# crystal.net
KiCad netlist of a schematic drawn in Altium Designer
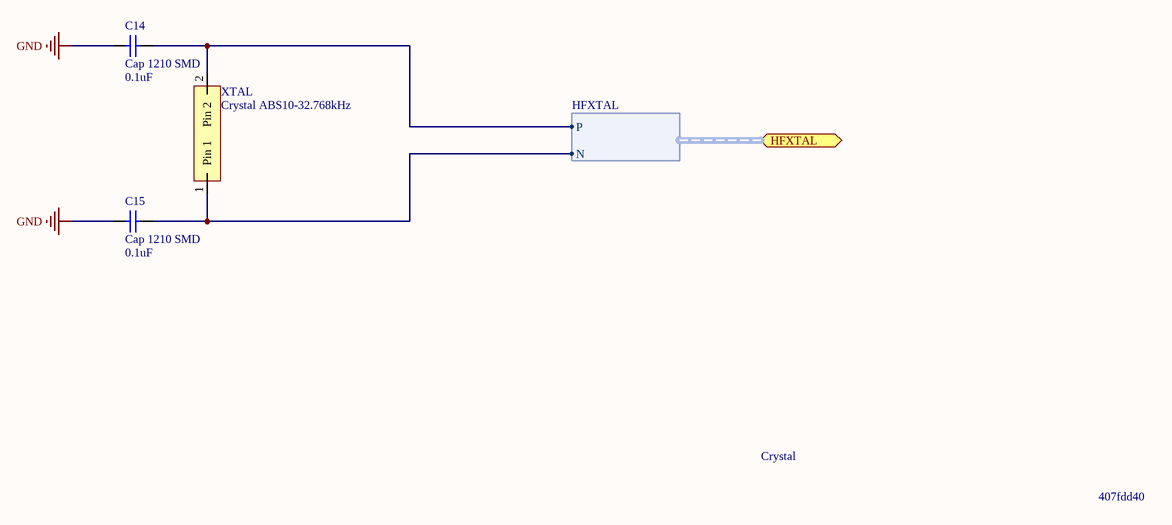
[diagram p0: crystal.schdoc]

(export (version "E")
  (design (tool "Eeschema 10.0.6"))
  (components
    (comp (ref "C14")
      (value "Cap 1210 SMD")
      (footprint "CAPC1210(3225)100_L")
      (description "CAP 0.1uF 100V ±1% 1210 (3225 Metric) Thickness 1mm SMD")
      (fields (field (name "ALTIUM_VALUE") "0.1uF") (field (name "TOLERANCE") "±1%"))
      (libsource (lib "Altium Content Vault") (part "CMP-1038-00186-1"))
    )
    (comp (ref "C15")
      (value "Cap 1210 SMD")
      (footprint "CAPC1210(3225)100_L")
      (description "CAP 0.1uF 100V ±1% 1210 (3225 Metric) Thickness 1mm SMD")
      (fields (field (name "ALTIUM_VALUE") "0.1uF") (field (name "TOLERANCE") "±1%"))
      (libsource (lib "Altium Content Vault") (part "CMP-1038-00186-1"))
    )
    (comp (ref "XTAL")
      (value "Crystal ABS10-32.768kHz")
      (footprint "crystal-footprint:crystal-ABS10-32.768KHZ-T")
      (libsource (lib "crystal") (part "Crystal ABS10-32.768kHz"))
    )
  )
  (nets
    (net (code "3") (name "GND") (class "Default")
      (node (ref "C14") (pin "2") (pinfunction "2_2") (pintype "passive"))
      (node (ref "C15") (pin "1") (pinfunction "1_1") (pintype "passive"))
    )
    (net (code "4") (name "Net-(XTAL-Pin_1)") (class "Default")
      (node (ref "C15") (pin "2") (pinfunction "2_2") (pintype "passive"))
      (node (ref "XTAL") (pin "1") (pinfunction "Pin_1_1") (pintype "passive"))
    )
    (net (code "5") (name "Net-(XTAL-Pin_2)") (class "Default")
      (node (ref "C14") (pin "1") (pinfunction "1_1") (pintype "passive"))
      (node (ref "XTAL") (pin "2") (pinfunction "Pin_2_2") (pintype "passive"))
    )
  )
)
